# bg_sensor.net
KiCad netlist of a schematic drawn in Altium Designer
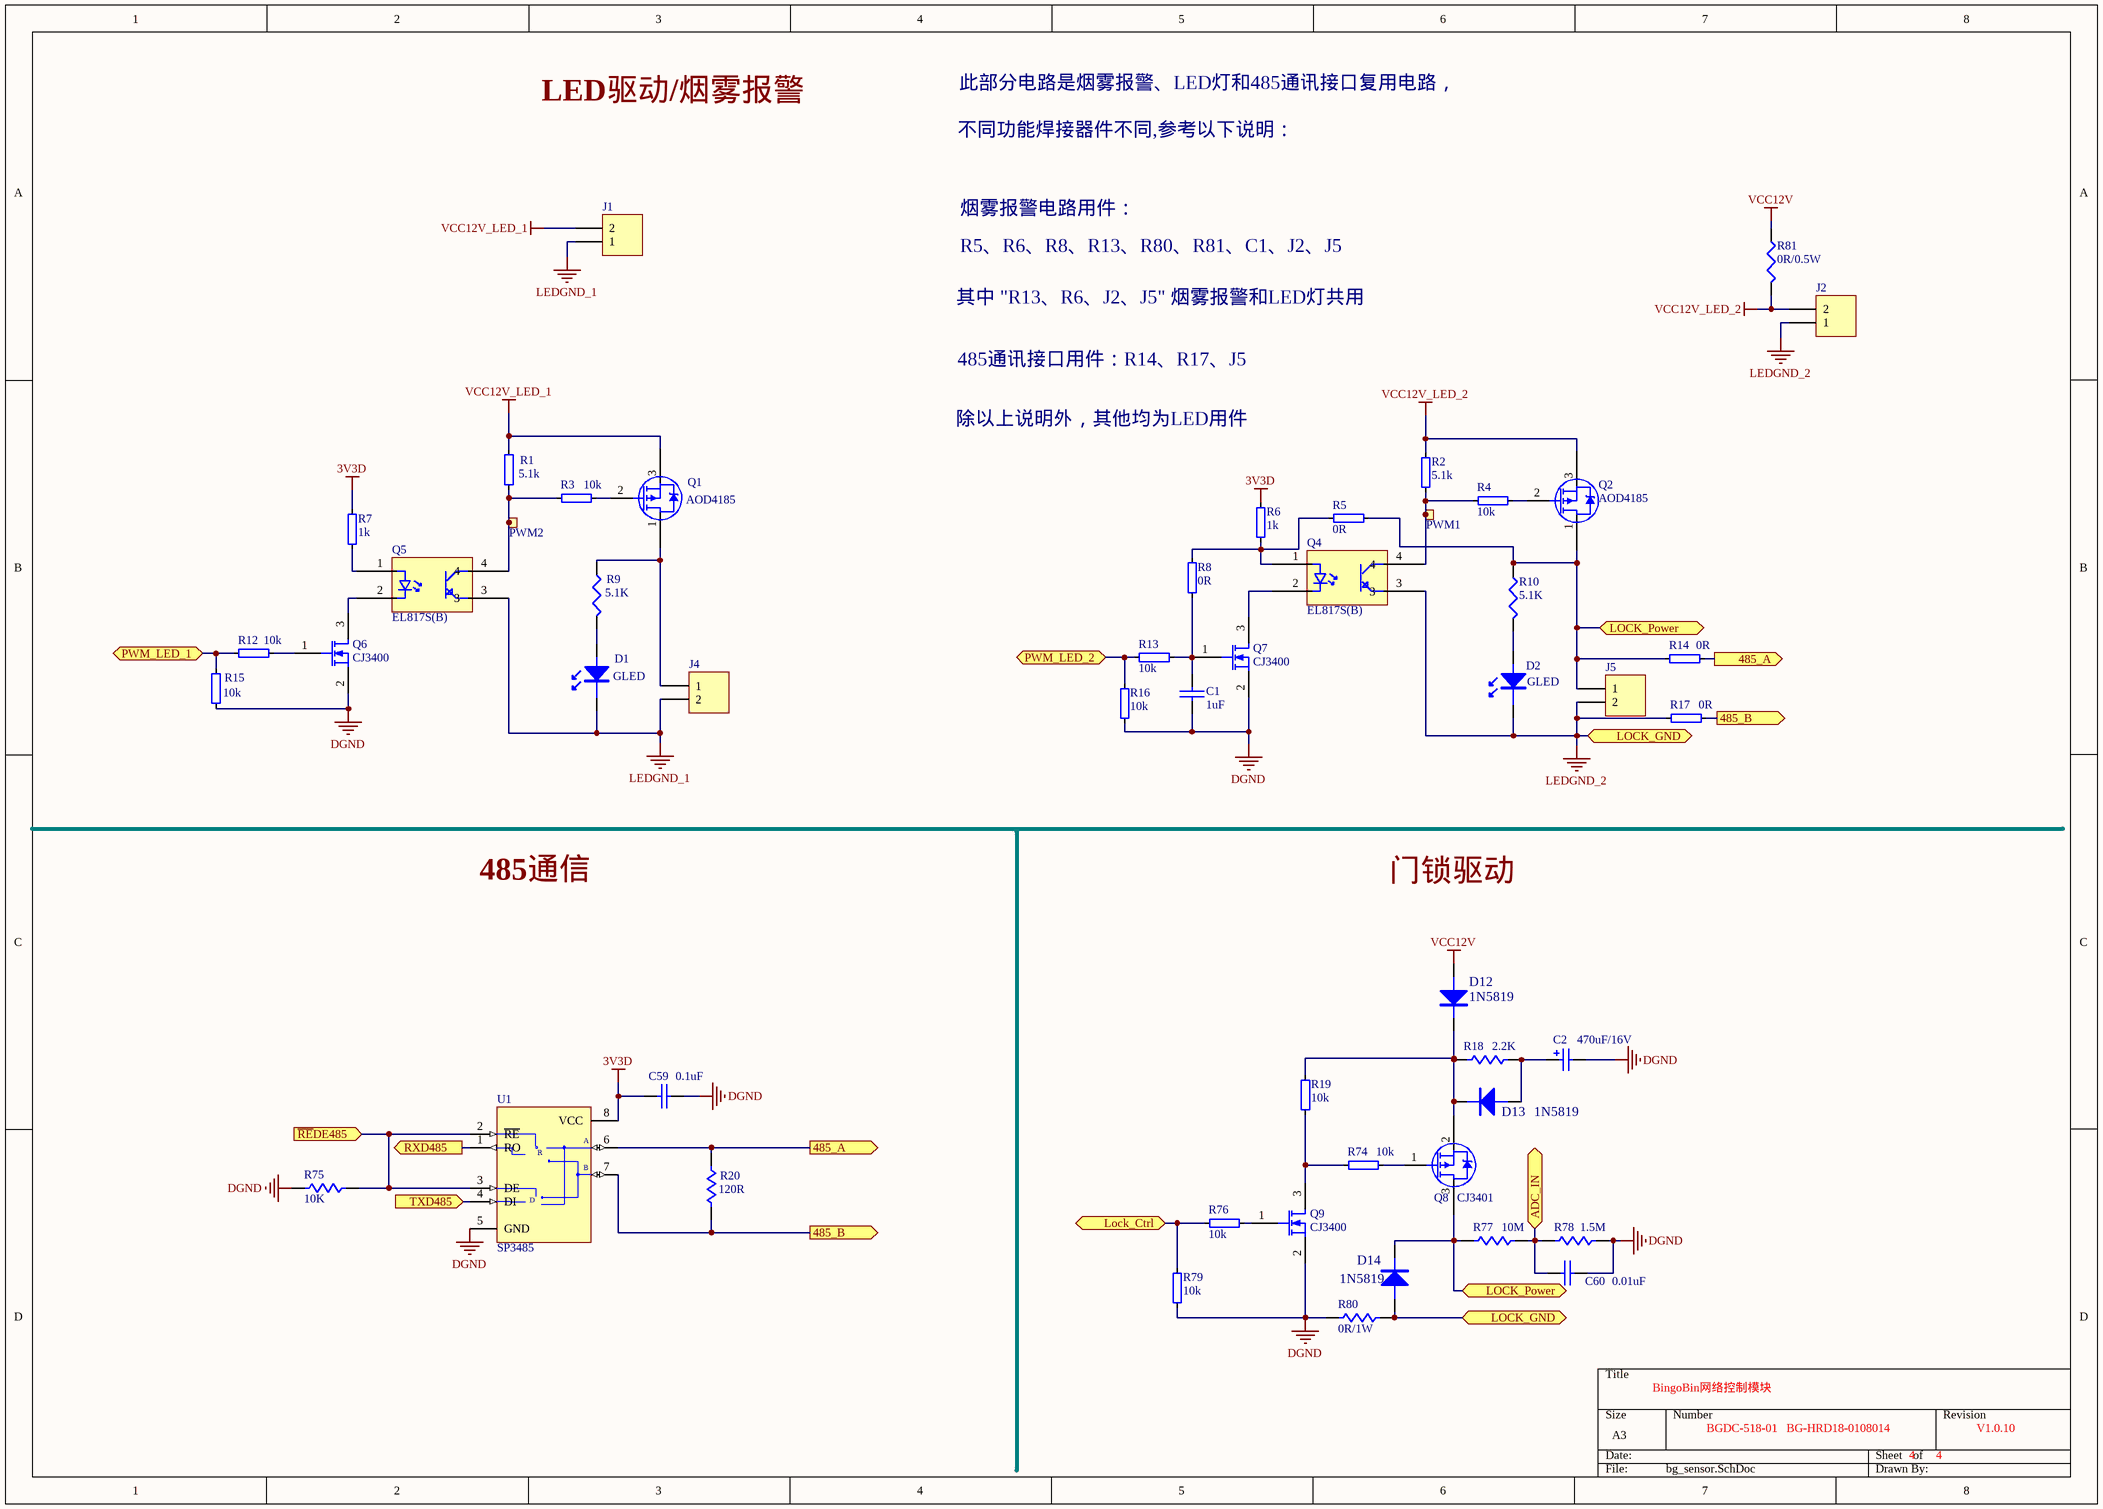
[diagram p0: bg_sensor.SchDoc]

(export (version "E")
  (design (tool "Eeschema 10.0.6"))
  (components
    (comp (ref "C1")
      (value "1uF")
      (footprint "C0603")
      (description "Capacitor, Ceramic, 0.1uF, 16V, 10%, 0603, X7R")
      (libsource (lib "bg_sch") (part "C0603"))
    )
    (comp (ref "C2")
      (value "470uF/16V")
      (footprint "C10*10.5mm")
      (description "Capacitor, Aluminum Electrolytic, 470uF,16V, 20%")
      (fields (field (name "PUBLISHER") "Altium Limited"))
      (libsource (lib "Miscellaneous Devices") (part "Cap Pol2"))
    )
    (comp (ref "C59")
      (value "0.1uF")
      (footprint "C0603")
      (description "Capacitor, Ceramic, 0.1uF, 16V, 10%, 0603, X7R")
      (libsource (lib "bg_sch") (part "C0603"))
    )
    (comp (ref "C60")
      (value "0.01uF")
      (footprint "C0603")
      (description "Capacitor, Ceramic, 0.1uF, 16V, 10%, 0603, X7R")
      (libsource (lib "bg_sch") (part "C0603"))
    )
    (comp (ref "D1")
      (value "GLED")
      (footprint "LED-0805")
      (description "翠绿色 贴片LED ( Iv=220-270mcd @IF=5mA) ")
      (libsource (lib "bg_sch") (part "LED_0805"))
    )
    (comp (ref "D2")
      (value "GLED")
      (footprint "LED-0805")
      (description "翠绿色 贴片LED ( Iv=220-270mcd @IF=5mA) ")
      (libsource (lib "bg_sch") (part "LED_0805"))
    )
    (comp (ref "D12")
      (value "1N5819")
      (footprint "SOD123")
      (description "Diode Schottky, 40V,1A")
      (libsource (lib "*") (part "DIODE"))
    )
    (comp (ref "D13")
      (value "1N5819")
      (footprint "SOD123")
      (description "Diode Schottky, 40V,1A")
      (libsource (lib "*") (part "DIODE"))
    )
    (comp (ref "D14")
      (value "1N5819")
      (footprint "SOD123")
      (description "Diode Schottky, 40V,1A")
      (libsource (lib "*") (part "DIODE"))
    )
    (comp (ref "J1")
      (value "36-57VDC RTN")
      (footprint "MKDS_5_6.35")
      (description "WJ15EDGVC-3.81-2P")
      (fields (field (name "PUBLISHER") "Altium Limited"))
      (libsource (lib "") (part "Header 2_1"))
    )
    (comp (ref "J2")
      (value "36-57VDC RTN")
      (footprint "MKDS_5_6.35")
      (description "WJ15EDGVC-3.81-2P")
      (fields (field (name "PUBLISHER") "Altium Limited"))
      (libsource (lib "") (part "Header 2_1"))
    )
    (comp (ref "J4")
      (value "36-57VDC RTN")
      (footprint "MKDS_5_6.35")
      (description "WJ15EDGVC-3.81-2P")
      (fields (field (name "PUBLISHER") "Altium Limited"))
      (libsource (lib "Miscellaneous Connectors") (part "Header 2"))
    )
    (comp (ref "J5")
      (value "36-57VDC RTN")
      (footprint "MKDS_5_6.35")
      (description "WJ15EDGVC-3.81-2P")
      (fields (field (name "PUBLISHER") "Altium Limited"))
      (libsource (lib "Miscellaneous Connectors") (part "Header 2"))
    )
    (comp (ref "PWM1")
      (value "?.0mm,SMD")
      (footprint "TP_SMD_1mm")
      (description "1.0mm circular SMD testpad")
      (fields
        (field (name "PART NUMBER") "TP_SMD_?.0MM")
        (field (name "MANUFACTURER") "Nordic Semiconductor")
        (field (name "PUBLISHER") "Nordic Semiconductor")
      )
      (libsource (lib "bingo") (part "TESTPAD"))
    )
    (comp (ref "PWM2")
      (value "?.0mm,SMD")
      (footprint "TP_SMD_1mm")
      (description "1.0mm circular SMD testpad")
      (fields
        (field (name "PART NUMBER") "TP_SMD_?.0MM")
        (field (name "MANUFACTURER") "Nordic Semiconductor")
        (field (name "PUBLISHER") "Nordic Semiconductor")
      )
      (libsource (lib "bingo") (part "TESTPAD"))
    )
    (comp (ref "Q1")
      (value "AOD4185")
      (footprint "TO252")
      (description "AOD4185(TO-252-2)")
      (libsource (lib "bingo") (part "PMOS"))
    )
    (comp (ref "Q2")
      (value "AOD4185")
      (footprint "TO252")
      (description "AOD4185(TO-252-2)")
      (libsource (lib "bingo") (part "PMOS"))
    )
    (comp (ref "Q4")
      (value "EL817S(B)")
      (footprint "LC_SMD-4")
      (description "EL817S(B)(TU)-F")
      (libsource (lib "bingo") (part "Optocoupler"))
    )
    (comp (ref "Q5")
      (value "EL817S(B)")
      (footprint "LC_SMD-4")
      (description "EL817S(B)(TU)-F")
      (libsource (lib "bingo") (part "Optocoupler"))
    )
    (comp (ref "Q6")
      (value "CJ3400")
      (footprint "sot-23")
      (description "N沟道,30V,5.6A,27mΩ(Typ,@Vgs=4.5V)")
      (fields (field (name "PUBLISHER") "Altium Limited"))
      (libsource (lib "Miscellaneous Devices") (part "MOSFET-N"))
    )
    (comp (ref "Q7")
      (value "CJ3400")
      (footprint "sot-23")
      (description "N沟道,30V,5.6A,27mΩ(Typ,@Vgs=4.5V)")
      (fields (field (name "PUBLISHER") "Altium Limited"))
      (libsource (lib "Miscellaneous Devices") (part "MOSFET-N"))
    )
    (comp (ref "Q8")
      (value "CJ3401")
      (footprint "sot-23")
      (description "CJ3401(SOT-23-3)")
      (libsource (lib "bingo") (part "PMOS-2"))
    )
    (comp (ref "Q9")
      (value "CJ3400")
      (footprint "sot-23")
      (description "N沟道,30V,5.6A,27mΩ(Typ,@Vgs=4.5V)")
      (fields (field (name "PUBLISHER") "Altium Limited"))
      (libsource (lib "Miscellaneous Devices") (part "MOSFET-N"))
    )
    (comp (ref "R1")
      (value "5.1k")
      (footprint "R0603")
      (description "RES, THICK FILM, 10K, 5%, 1/10W, 0603")
      (fields (field (name "PART NUMBER") "R0402-10k") (field (name "PUBLISHER") "Nordic Semiconductor"))
      (libsource (lib "Nordic Passive DB") (part "RES_1"))
    )
    (comp (ref "R2")
      (value "5.1k")
      (footprint "R0603")
      (description "RES, THICK FILM, 10K, 5%, 1/10W, 0603")
      (fields (field (name "PART NUMBER") "R0402-10k") (field (name "PUBLISHER") "Nordic Semiconductor"))
      (libsource (lib "Nordic Passive DB") (part "RES_1"))
    )
    (comp (ref "R3")
      (value "10k")
      (footprint "R0603")
      (description "RES, THICK FILM, 10K, 5%, 1/10W, 0603")
      (fields (field (name "PART NUMBER") "R0402-10k") (field (name "PUBLISHER") "Nordic Semiconductor"))
      (libsource (lib "Nordic Passive DB") (part "RES_1"))
    )
    (comp (ref "R4")
      (value "10k")
      (footprint "R0603")
      (description "RES, THICK FILM, 10K, 5%, 1/10W, 0603")
      (fields (field (name "PART NUMBER") "R0402-10k") (field (name "PUBLISHER") "Nordic Semiconductor"))
      (libsource (lib "Nordic Passive DB") (part "RES_1"))
    )
    (comp (ref "R5")
      (value "0R")
      (footprint "R0603")
      (description "RES, THICK FILM, 10K, 5%, 1/10W, 0603")
      (fields (field (name "PART NUMBER") "R0402-10k") (field (name "PUBLISHER") "Nordic Semiconductor"))
      (libsource (lib "Nordic Passive DB") (part "RES_1"))
    )
    (comp (ref "R6")
      (value "1k")
      (footprint "R0603")
      (description "RES, THICK FILM, 10K, 5%, 1/10W, 0603")
      (fields (field (name "PART NUMBER") "R0402-10k") (field (name "PUBLISHER") "Nordic Semiconductor"))
      (libsource (lib "Nordic Passive DB") (part "RES_1"))
    )
    (comp (ref "R7")
      (value "1k")
      (footprint "R0603")
      (description "RES, THICK FILM, 10K, 5%, 1/10W, 0603")
      (fields (field (name "PART NUMBER") "R0402-10k") (field (name "PUBLISHER") "Nordic Semiconductor"))
      (libsource (lib "Nordic Passive DB") (part "RES_1"))
    )
    (comp (ref "R8")
      (value "0R")
      (footprint "R0603")
      (description "RES, THICK FILM, 10K, 5%, 1/10W, 0603")
      (fields (field (name "PART NUMBER") "R0402-10k") (field (name "PUBLISHER") "Nordic Semiconductor"))
      (libsource (lib "Nordic Passive DB") (part "RES_1"))
    )
    (comp (ref "R9")
      (value "5.1K")
      (footprint "R0603")
      (description "RES, THICK FILM, 1K, 5%, 1/10W, 0603")
      (fields (field (name "PUBLISHER") "Altium Limited"))
      (libsource (lib "Miscellaneous Devices") (part "Res3"))
    )
    (comp (ref "R10")
      (value "5.1K")
      (footprint "R0603")
      (description "RES, THICK FILM, 1K, 5%, 1/10W, 0603")
      (fields (field (name "PUBLISHER") "Altium Limited"))
      (libsource (lib "Miscellaneous Devices") (part "Res3"))
    )
    (comp (ref "R12")
      (value "10k")
      (footprint "R0603")
      (description "RES, THICK FILM, 10K, 5%, 1/10W, 0603")
      (fields (field (name "PART NUMBER") "R0402-10k") (field (name "PUBLISHER") "Nordic Semiconductor"))
      (libsource (lib "Nordic Passive DB") (part "RES_1"))
    )
    (comp (ref "R13")
      (value "10k")
      (footprint "R0603")
      (description "RES, THICK FILM, 10K, 5%, 1/10W, 0603")
      (fields (field (name "PART NUMBER") "R0402-10k") (field (name "PUBLISHER") "Nordic Semiconductor"))
      (libsource (lib "Nordic Passive DB") (part "RES_1"))
    )
    (comp (ref "R14")
      (value "0R")
      (footprint "R0603")
      (description "RES, THICK FILM, 10K, 5%, 1/10W, 0603")
      (fields (field (name "PART NUMBER") "R0402-10k") (field (name "PUBLISHER") "Nordic Semiconductor"))
      (libsource (lib "Nordic Passive DB") (part "RES_1"))
    )
    (comp (ref "R15")
      (value "10k")
      (footprint "R0603")
      (description "RES, THICK FILM, 10K, 5%, 1/10W, 0603")
      (fields (field (name "PART NUMBER") "R0402-10k") (field (name "PUBLISHER") "Nordic Semiconductor"))
      (libsource (lib "Nordic Passive DB") (part "RES_1"))
    )
    (comp (ref "R16")
      (value "10k")
      (footprint "R0603")
      (description "RES, THICK FILM, 10K, 5%, 1/10W, 0603")
      (fields (field (name "PART NUMBER") "R0402-10k") (field (name "PUBLISHER") "Nordic Semiconductor"))
      (libsource (lib "Nordic Passive DB") (part "RES_1"))
    )
    (comp (ref "R17")
      (value "0R")
      (footprint "R0603")
      (description "RES, THICK FILM, 10K, 5%, 1/10W, 0603")
      (fields (field (name "PART NUMBER") "R0402-10k") (field (name "PUBLISHER") "Nordic Semiconductor"))
      (libsource (lib "Nordic Passive DB") (part "RES_1"))
    )
    (comp (ref "R18")
      (value "2.2K")
      (footprint "0805")
      (description "RES, THICK FILM, 2.2K, 5%, 1/8W, 0805")
      (libsource (lib "bg_sch") (part "R0603"))
    )
    (comp (ref "R19")
      (value "10k")
      (footprint "R0603")
      (description "RES, THICK FILM, 10K, 5%, 1/10W, 0603")
      (fields (field (name "PART NUMBER") "R0402-10k") (field (name "PUBLISHER") "Nordic Semiconductor"))
      (libsource (lib "Nordic Passive DB") (part "RES_1"))
    )
    (comp (ref "R20")
      (value "120R")
      (footprint "R0603")
      (description "RES, THICK FILM, 120 OHM, 5%, 1/10W, 0603")
      (libsource (lib "bg_sch") (part "R0603"))
    )
    (comp (ref "R74")
      (value "10k")
      (footprint "R0603")
      (description "RES, THICK FILM, 10K, 5%, 1/10W, 0603")
      (fields (field (name "PART NUMBER") "R0402-10k") (field (name "PUBLISHER") "Nordic Semiconductor"))
      (libsource (lib "Nordic Passive DB") (part "RES_1"))
    )
    (comp (ref "R75")
      (value "10K")
      (footprint "R0603")
      (description "RES, THICK FILM, 10K, 5%, 1/10W, 0603")
      (libsource (lib "bg_sch") (part "R0603"))
    )
    (comp (ref "R76")
      (value "10k")
      (footprint "R0603")
      (description "RES, THICK FILM, 10K, 5%, 1/10W, 0603")
      (fields (field (name "PART NUMBER") "R0402-10k") (field (name "PUBLISHER") "Nordic Semiconductor"))
      (libsource (lib "Nordic Passive DB") (part "RES_1"))
    )
    (comp (ref "R77")
      (value "10M")
      (footprint "R0603")
      (description "RES, THICK FILM, 10M, 5%, 1/10W, 0603")
      (libsource (lib "bg_sch") (part "R0603"))
    )
    (comp (ref "R78")
      (value "1.5M")
      (footprint "R0603")
      (description "RES, THICK FILM, 1.5M, 5%, 1/10W, 0603")
      (libsource (lib "bg_sch") (part "R0603"))
    )
    (comp (ref "R79")
      (value "10k")
      (footprint "R0603")
      (description "RES, THICK FILM, 10K, 5%, 1/10W, 0603")
      (fields (field (name "PART NUMBER") "R0402-10k") (field (name "PUBLISHER") "Nordic Semiconductor"))
      (libsource (lib "Nordic Passive DB") (part "RES_1"))
    )
    (comp (ref "R80")
      (value "0R/1W")
      (footprint "2512")
      (description "RES, THICK FILM, 1.5M, 5%, 1/10W, 0603")
      (libsource (lib "bg_sch") (part "R0603"))
    )
    (comp (ref "R81")
      (value "0R/0.5W")
      (footprint "1206")
      (description "RES, THICK FILM, 0.39 OHM, 1%, 3/4W, 2010")
      (fields (field (name "PUBLISHER") "Altium Limited"))
      (libsource (lib "Miscellaneous Devices") (part "Res3"))
    )
    (comp (ref "U1")
      (value "SP3485")
      (footprint "SOIC8")
      (description "+3.3V Low Power Half-Duplex RS-485 Transceiver with 10Mbps Data Rate")
      (libsource (lib "SP3485Sch") (part "SP3485"))
    )
  )
  (nets
    (net (code "1") (name "/485_A") (class "Default")
      (node (ref "R14") (pin "2") (pinfunction "2_2") (pintype "passive"))
      (node (ref "R20") (pin "2") (pinfunction "2_2") (pintype "passive"))
      (node (ref "U1") (pin "6") (pinfunction "A_6") (pintype "bidirectional"))
    )
    (net (code "2") (name "/485_B") (class "Default")
      (node (ref "R17") (pin "2") (pinfunction "2_2") (pintype "passive"))
      (node (ref "R20") (pin "1") (pinfunction "1_1") (pintype "passive"))
      (node (ref "U1") (pin "7") (pinfunction "B_7") (pintype "bidirectional"))
    )
    (net (code "3") (name "/ADC_IN") (class "Default")
      (node (ref "C60") (pin "1") (pinfunction "1_1") (pintype "passive"))
      (node (ref "R77") (pin "1") (pinfunction "1_1") (pintype "passive"))
      (node (ref "R78") (pin "2") (pinfunction "2_2") (pintype "passive"))
    )
    (net (code "4") (name "/LOCK_Power") (class "Default")
      (node (ref "D14") (pin "2") (pinfunction "K_2") (pintype "passive"))
      (node (ref "J5") (pin "1") (pinfunction "1_1") (pintype "passive"))
      (node (ref "Q2") (pin "1") (pinfunction "D_1") (pintype "passive"))
      (node (ref "Q8") (pin "3") (pinfunction "D_3") (pintype "passive"))
      (node (ref "R10") (pin "1") (pinfunction "1_1") (pintype "passive"))
      (node (ref "R14") (pin "1") (pinfunction "1_1") (pintype "passive"))
      (node (ref "R5") (pin "1") (pinfunction "1_1") (pintype "passive"))
      (node (ref "R77") (pin "2") (pinfunction "2_2") (pintype "passive"))
    )
    (net (code "5") (name "/Lock_Ctrl") (class "Default")
      (node (ref "R76") (pin "1") (pinfunction "1_1") (pintype "passive"))
      (node (ref "R79") (pin "2") (pinfunction "2_2") (pintype "passive"))
    )
    (net (code "6") (name "/PWM_LED_1") (class "Default")
      (node (ref "R12") (pin "1") (pinfunction "1_1") (pintype "passive"))
      (node (ref "R15") (pin "2") (pinfunction "2_2") (pintype "passive"))
    )
    (net (code "7") (name "/PWM_LED_2") (class "Default")
      (node (ref "R13") (pin "1") (pinfunction "1_1") (pintype "passive"))
      (node (ref "R16") (pin "2") (pinfunction "2_2") (pintype "passive"))
    )
    (net (code "8") (name "/RXD485") (class "Default")
      (node (ref "U1") (pin "1") (pinfunction "RO_1") (pintype "output"))
    )
    (net (code "9") (name "/TXD485") (class "Default")
      (node (ref "U1") (pin "4") (pinfunction "DI_4") (pintype "input"))
    )
    (net (code "10") (name "/~{RE}DE485") (class "Default")
      (node (ref "R75") (pin "1") (pinfunction "1_1") (pintype "passive"))
      (node (ref "U1") (pin "2") (pinfunction "~{RE}_2") (pintype "input"))
      (node (ref "U1") (pin "3") (pinfunction "DE_3") (pintype "input"))
    )
    (net (code "11") (name "3V3D") (class "Default")
      (node (ref "C59") (pin "1") (pinfunction "1_1") (pintype "passive"))
      (node (ref "R6") (pin "2") (pinfunction "2_2") (pintype "passive"))
      (node (ref "R7") (pin "2") (pinfunction "2_2") (pintype "passive"))
      (node (ref "U1") (pin "8") (pinfunction "VCC_8") (pintype "power_in"))
    )
    (net (code "12") (name "DGND") (class "Default")
      (node (ref "C1") (pin "1") (pinfunction "1_1") (pintype "passive"))
      (node (ref "C2") (pin "2") (pinfunction "2_2") (pintype "passive"))
      (node (ref "C59") (pin "2") (pinfunction "2_2") (pintype "passive"))
      (node (ref "C60") (pin "2") (pinfunction "2_2") (pintype "passive"))
      (node (ref "Q6") (pin "2") (pinfunction "S_2") (pintype "passive"))
      (node (ref "Q7") (pin "2") (pinfunction "S_2") (pintype "passive"))
      (node (ref "Q9") (pin "2") (pinfunction "S_2") (pintype "passive"))
      (node (ref "R15") (pin "1") (pinfunction "1_1") (pintype "passive"))
      (node (ref "R16") (pin "1") (pinfunction "1_1") (pintype "passive"))
      (node (ref "R75") (pin "2") (pinfunction "2_2") (pintype "passive"))
      (node (ref "R78") (pin "1") (pinfunction "1_1") (pintype "passive"))
      (node (ref "R79") (pin "1") (pinfunction "1_1") (pintype "passive"))
      (node (ref "R80") (pin "2") (pinfunction "2_2") (pintype "passive"))
      (node (ref "U1") (pin "5") (pinfunction "GND_5") (pintype "power_in"))
    )
    (net (code "13") (name "LEDGND_1") (class "Default")
      (node (ref "D1") (pin "2") (pinfunction "2_2") (pintype "passive"))
      (node (ref "J1") (pin "1") (pinfunction "1_1") (pintype "passive"))
      (node (ref "J4") (pin "2") (pinfunction "2_2") (pintype "passive"))
      (node (ref "Q5") (pin "3") (pinfunction "3_3") (pintype "passive"))
    )
    (net (code "14") (name "LEDGND_2") (class "Default")
      (node (ref "D14") (pin "1") (pinfunction "A_1") (pintype "passive"))
      (node (ref "D2") (pin "2") (pinfunction "2_2") (pintype "passive"))
      (node (ref "J2") (pin "1") (pinfunction "1_1") (pintype "passive"))
      (node (ref "J5") (pin "2") (pinfunction "2_2") (pintype "passive"))
      (node (ref "Q4") (pin "3") (pinfunction "3_3") (pintype "passive"))
      (node (ref "R17") (pin "1") (pinfunction "1_1") (pintype "passive"))
      (node (ref "R80") (pin "1") (pinfunction "1_1") (pintype "passive"))
    )
    (net (code "15") (name "Net-(D1-Pad1)") (class "Default")
      (node (ref "D1") (pin "1") (pinfunction "1_1") (pintype "passive"))
      (node (ref "R9") (pin "2") (pinfunction "2_2") (pintype "passive"))
    )
    (net (code "16") (name "Net-(D2-Pad1)") (class "Default")
      (node (ref "D2") (pin "1") (pinfunction "1_1") (pintype "passive"))
      (node (ref "R10") (pin "2") (pinfunction "2_2") (pintype "passive"))
    )
    (net (code "17") (name "Net-(D12-K)") (class "Default")
      (node (ref "D12") (pin "2") (pinfunction "K_2") (pintype "passive"))
      (node (ref "D13") (pin "2") (pinfunction "K_2") (pintype "passive"))
      (node (ref "Q8") (pin "2") (pinfunction "S_2") (pintype "passive"))
      (node (ref "R18") (pin "1") (pinfunction "1_1") (pintype "passive"))
      (node (ref "R19") (pin "2") (pinfunction "2_2") (pintype "passive"))
    )
    (net (code "18") (name "Net-(D13-A)") (class "Default")
      (node (ref "C2") (pin "1") (pinfunction "1_1") (pintype "passive"))
      (node (ref "D13") (pin "1") (pinfunction "A_1") (pintype "passive"))
      (node (ref "R18") (pin "2") (pinfunction "2_2") (pintype "passive"))
    )
    (net (code "19") (name "Net-(PWM1-Pad1)") (class "Default")
      (node (ref "PWM1") (pin "1") (pinfunction "1_1") (pintype "passive"))
      (node (ref "Q4") (pin "4") (pinfunction "4_4") (pintype "passive"))
      (node (ref "R2") (pin "1") (pinfunction "1_1") (pintype "passive"))
      (node (ref "R4") (pin "1") (pinfunction "1_1") (pintype "passive"))
    )
    (net (code "20") (name "Net-(PWM2-Pad1)") (class "Default")
      (node (ref "PWM2") (pin "1") (pinfunction "1_1") (pintype "passive"))
      (node (ref "Q5") (pin "4") (pinfunction "4_4") (pintype "passive"))
      (node (ref "R1") (pin "1") (pinfunction "1_1") (pintype "passive"))
      (node (ref "R3") (pin "1") (pinfunction "1_1") (pintype "passive"))
    )
    (net (code "21") (name "Net-(Q1-D)") (class "Default")
      (node (ref "J4") (pin "1") (pinfunction "1_1") (pintype "passive"))
      (node (ref "Q1") (pin "1") (pinfunction "D_1") (pintype "passive"))
      (node (ref "R9") (pin "1") (pinfunction "1_1") (pintype "passive"))
    )
    (net (code "22") (name "Net-(Q1-G)") (class "Default")
      (node (ref "Q1") (pin "2") (pinfunction "G_2") (pintype "passive"))
      (node (ref "R3") (pin "2") (pinfunction "2_2") (pintype "passive"))
    )
    (net (code "23") (name "Net-(Q2-G)") (class "Default")
      (node (ref "Q2") (pin "2") (pinfunction "G_2") (pintype "passive"))
      (node (ref "R4") (pin "2") (pinfunction "2_2") (pintype "passive"))
    )
    (net (code "24") (name "Net-(Q4-Pad1)") (class "Default")
      (node (ref "Q4") (pin "1") (pinfunction "1_1") (pintype "passive"))
      (node (ref "R5") (pin "2") (pinfunction "2_2") (pintype "passive"))
      (node (ref "R6") (pin "1") (pinfunction "1_1") (pintype "passive"))
      (node (ref "R8") (pin "1") (pinfunction "1_1") (pintype "passive"))
    )
    (net (code "25") (name "Net-(Q5-Pad1)") (class "Default")
      (node (ref "Q5") (pin "1") (pinfunction "1_1") (pintype "passive"))
      (node (ref "R7") (pin "1") (pinfunction "1_1") (pintype "passive"))
    )
    (net (code "26") (name "Net-(Q6-D)") (class "Default")
      (node (ref "Q5") (pin "2") (pinfunction "2_2") (pintype "passive"))
      (node (ref "Q6") (pin "3") (pinfunction "D_3") (pintype "passive"))
    )
    (net (code "27") (name "Net-(Q6-G)") (class "Default")
      (node (ref "Q6") (pin "1") (pinfunction "G_1") (pintype "passive"))
      (node (ref "R12") (pin "2") (pinfunction "2_2") (pintype "passive"))
    )
    (net (code "28") (name "Net-(Q7-D)") (class "Default")
      (node (ref "Q4") (pin "2") (pinfunction "2_2") (pintype "passive"))
      (node (ref "Q7") (pin "3") (pinfunction "D_3") (pintype "passive"))
    )
    (net (code "29") (name "Net-(Q7-G)") (class "Default")
      (node (ref "C1") (pin "2") (pinfunction "2_2") (pintype "passive"))
      (node (ref "Q7") (pin "1") (pinfunction "G_1") (pintype "passive"))
      (node (ref "R13") (pin "2") (pinfunction "2_2") (pintype "passive"))
      (node (ref "R8") (pin "2") (pinfunction "2_2") (pintype "passive"))
    )
    (net (code "30") (name "Net-(Q8-G)") (class "Default")
      (node (ref "Q8") (pin "1") (pinfunction "G_1") (pintype "passive"))
      (node (ref "R74") (pin "2") (pinfunction "2_2") (pintype "passive"))
    )
    (net (code "31") (name "Net-(Q9-D)") (class "Default")
      (node (ref "Q9") (pin "3") (pinfunction "D_3") (pintype "passive"))
      (node (ref "R19") (pin "1") (pinfunction "1_1") (pintype "passive"))
      (node (ref "R74") (pin "1") (pinfunction "1_1") (pintype "passive"))
    )
    (net (code "32") (name "Net-(Q9-G)") (class "Default")
      (node (ref "Q9") (pin "1") (pinfunction "G_1") (pintype "passive"))
      (node (ref "R76") (pin "2") (pinfunction "2_2") (pintype "passive"))
    )
    (net (code "33") (name "VCC12V") (class "Default")
      (node (ref "D12") (pin "1") (pinfunction "A_1") (pintype "passive"))
      (node (ref "R81") (pin "1") (pinfunction "1_1") (pintype "passive"))
    )
    (net (code "34") (name "VCC12V_LED_1") (class "Default")
      (node (ref "J1") (pin "2") (pinfunction "2_2") (pintype "passive"))
      (node (ref "Q1") (pin "3") (pinfunction "S_3") (pintype "passive"))
      (node (ref "R1") (pin "2") (pinfunction "2_2") (pintype "passive"))
    )
    (net (code "35") (name "VCC12V_LED_2") (class "Default")
      (node (ref "J2") (pin "2") (pinfunction "2_2") (pintype "passive"))
      (node (ref "Q2") (pin "3") (pinfunction "S_3") (pintype "passive"))
      (node (ref "R2") (pin "2") (pinfunction "2_2") (pintype "passive"))
      (node (ref "R81") (pin "2") (pinfunction "2_2") (pintype "passive"))
    )
  )
)
